# 6_led.net
KiCad netlist of a schematic drawn in Altium Designer
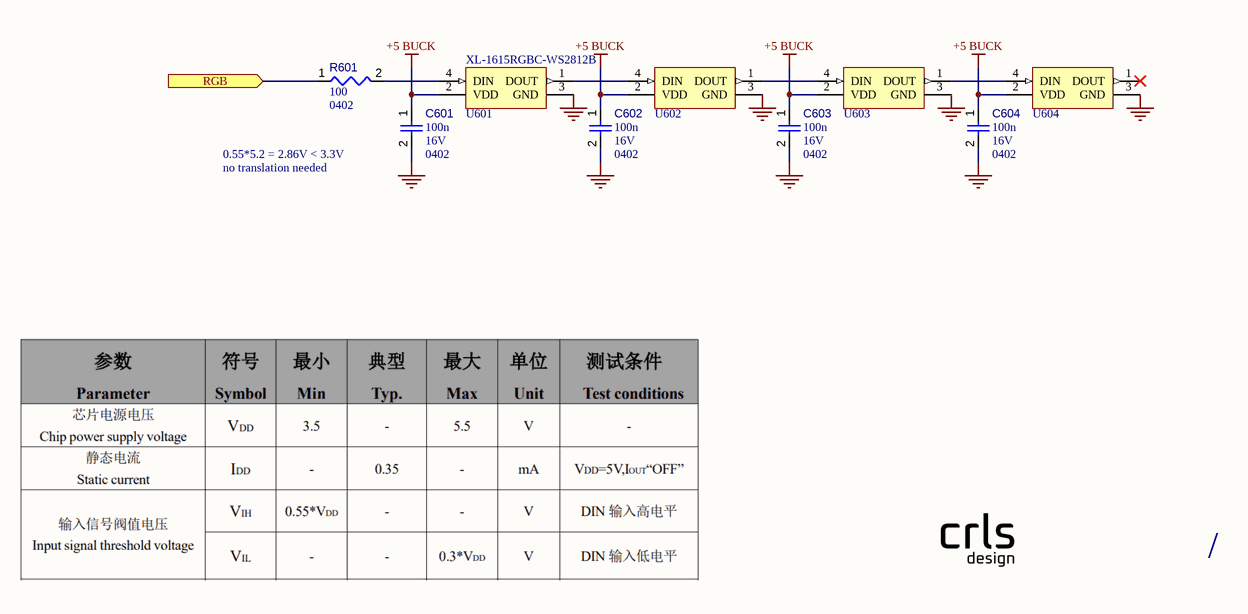
[diagram p0: 6 led.SchDoc]

(export (version "E")
  (design (tool "Eeschema 10.0.6"))
  (components
    (comp (ref "C601")
      (value "100n")
      (footprint "CAPC0402(1005)60_L")
      (description "Capacitor")
      (fields
        (field (name "CASE/PACKAGE") "0402")
        (field (name "VOLTAGE RATING") "16V")
        (field (name "Comment") "Capacitors,0402,100n,16V")
      )
      (libsource (lib "UBC Uncrewed Aircraft Systems") (part "CAP-NP-2"))
    )
    (comp (ref "C602")
      (value "100n")
      (footprint "CAPC0402(1005)60_L")
      (description "Capacitor")
      (fields
        (field (name "CASE/PACKAGE") "0402")
        (field (name "VOLTAGE RATING") "16V")
        (field (name "Comment") "Capacitors,0402,100n,16V")
      )
      (libsource (lib "UBC Uncrewed Aircraft Systems") (part "CAP-NP-2"))
    )
    (comp (ref "C603")
      (value "100n")
      (footprint "CAPC0402(1005)60_L")
      (description "Capacitor")
      (fields
        (field (name "CASE/PACKAGE") "0402")
        (field (name "VOLTAGE RATING") "16V")
        (field (name "Comment") "Capacitors,0402,100n,16V")
      )
      (libsource (lib "UBC Uncrewed Aircraft Systems") (part "CAP-NP-2"))
    )
    (comp (ref "C604")
      (value "100n")
      (footprint "CAPC0402(1005)60_L")
      (description "Capacitor")
      (fields
        (field (name "CASE/PACKAGE") "0402")
        (field (name "VOLTAGE RATING") "16V")
        (field (name "Comment") "Capacitors,0402,100n,16V")
      )
      (libsource (lib "UBC Uncrewed Aircraft Systems") (part "CAP-NP-2"))
    )
    (comp (ref "R601")
      (value "100")
      (footprint "RESC0402(1005)_L")
      (description "Resistor")
      (fields
        (field (name "CASE/PACKAGE") "0402")
        (field (name "TOLERANCE") "1%")
        (field (name "Comment") "Resistors,0402,1%,100")
      )
      (libsource (lib "UBC Uncrewed Aircraft Systems") (part "RES-2"))
    )
    (comp (ref "U601")
      (value "XL-1615RGBC-WS2812B")
      (footprint "WS2812B 1615")
      (libsource (lib "JLCPCB Library") (part "WS2812B 1615"))
    )
    (comp (ref "U602")
      (value "XL-1615RGBC-WS2812B")
      (footprint "WS2812B 1615")
      (libsource (lib "JLCPCB Library") (part "WS2812B 1615"))
    )
    (comp (ref "U603")
      (value "XL-1615RGBC-WS2812B")
      (footprint "WS2812B 1615")
      (libsource (lib "JLCPCB Library") (part "WS2812B 1615"))
    )
    (comp (ref "U604")
      (value "XL-1615RGBC-WS2812B")
      (footprint "WS2812B 1615")
      (libsource (lib "JLCPCB Library") (part "WS2812B 1615"))
    )
  )
  (nets
    (net (code "1") (name "+5 BUCK") (class "Default")
      (node (ref "C601") (pin "1") (pinfunction "1_1") (pintype "passive"))
      (node (ref "C602") (pin "1") (pinfunction "1_1") (pintype "passive"))
      (node (ref "C603") (pin "1") (pinfunction "1_1") (pintype "passive"))
      (node (ref "C604") (pin "1") (pinfunction "1_1") (pintype "passive"))
      (node (ref "U601") (pin "2") (pinfunction "VDD_2") (pintype "power_in"))
      (node (ref "U602") (pin "2") (pinfunction "VDD_2") (pintype "power_in"))
      (node (ref "U603") (pin "2") (pinfunction "VDD_2") (pintype "power_in"))
      (node (ref "U604") (pin "2") (pinfunction "VDD_2") (pintype "power_in"))
    )
    (net (code "2") (name "/RGB") (class "Default")
      (node (ref "R601") (pin "1") (pinfunction "1_1") (pintype "passive"))
    )
    (net (code "3") (name "GND") (class "Default")
      (node (ref "C601") (pin "2") (pinfunction "2_2") (pintype "passive"))
      (node (ref "C602") (pin "2") (pinfunction "2_2") (pintype "passive"))
      (node (ref "C603") (pin "2") (pinfunction "2_2") (pintype "passive"))
      (node (ref "C604") (pin "2") (pinfunction "2_2") (pintype "passive"))
      (node (ref "U601") (pin "3") (pinfunction "GND_3") (pintype "power_in"))
      (node (ref "U602") (pin "3") (pinfunction "GND_3") (pintype "power_in"))
      (node (ref "U603") (pin "3") (pinfunction "GND_3") (pintype "power_in"))
      (node (ref "U604") (pin "3") (pinfunction "GND_3") (pintype "power_in"))
    )
    (net (code "4") (name "Net-(U601-DIN)") (class "Default")
      (node (ref "R601") (pin "2") (pinfunction "2_2") (pintype "passive"))
      (node (ref "U601") (pin "4") (pinfunction "DIN_4") (pintype "input"))
    )
    (net (code "5") (name "Net-(U601-DOUT)") (class "Default")
      (node (ref "U601") (pin "1") (pinfunction "DOUT_1") (pintype "output"))
      (node (ref "U602") (pin "4") (pinfunction "DIN_4") (pintype "input"))
    )
    (net (code "6") (name "Net-(U602-DOUT)") (class "Default")
      (node (ref "U602") (pin "1") (pinfunction "DOUT_1") (pintype "output"))
      (node (ref "U603") (pin "4") (pinfunction "DIN_4") (pintype "input"))
    )
    (net (code "7") (name "Net-(U603-DOUT)") (class "Default")
      (node (ref "U603") (pin "1") (pinfunction "DOUT_1") (pintype "output"))
      (node (ref "U604") (pin "4") (pinfunction "DIN_4") (pintype "input"))
    )
    (net (code "8") (name "unconnected-(U604-DOUT-Pad1)") (class "Default")
      (node (ref "U604") (pin "1") (pinfunction "DOUT_1") (pintype "output+no_connect"))
    )
  )
)
